# main.net
KiCad netlist of a schematic drawn in Altium Designer
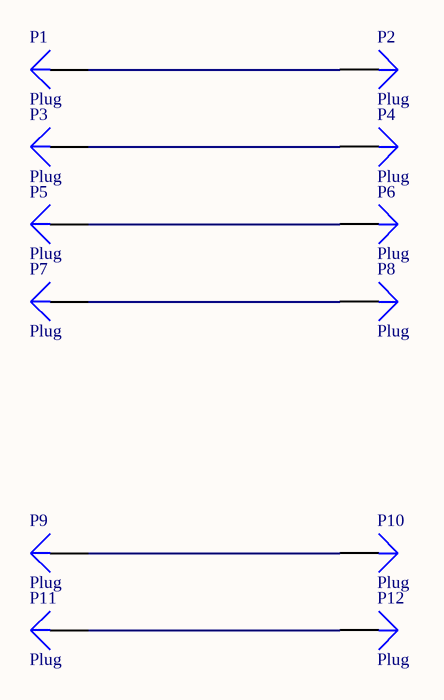
[diagram p0: main.SchDoc]

(export (version "E")
  (design (tool "Eeschema 10.0.6"))
  (components
    (comp (ref "P1")
      (value "Plug")
      (footprint "PIN_CONN")
      (fields (field (name "PUBLISHER") "Altium Limited"))
      (libsource (lib "Miscellaneous Connectors") (part "Plug"))
    )
    (comp (ref "P2")
      (value "Plug")
      (footprint "PIN_CONN")
      (fields (field (name "PUBLISHER") "Altium Limited"))
      (libsource (lib "Miscellaneous Connectors") (part "Plug"))
    )
    (comp (ref "P3")
      (value "Plug")
      (footprint "PIN_CONN")
      (fields (field (name "PUBLISHER") "Altium Limited"))
      (libsource (lib "Miscellaneous Connectors") (part "Plug"))
    )
    (comp (ref "P4")
      (value "Plug")
      (footprint "PIN_CONN")
      (fields (field (name "PUBLISHER") "Altium Limited"))
      (libsource (lib "Miscellaneous Connectors") (part "Plug"))
    )
    (comp (ref "P5")
      (value "Plug")
      (footprint "PIN_CONN")
      (fields (field (name "PUBLISHER") "Altium Limited"))
      (libsource (lib "Miscellaneous Connectors") (part "Plug"))
    )
    (comp (ref "P6")
      (value "Plug")
      (footprint "PIN_CONN")
      (fields (field (name "PUBLISHER") "Altium Limited"))
      (libsource (lib "Miscellaneous Connectors") (part "Plug"))
    )
    (comp (ref "P7")
      (value "Plug")
      (footprint "PIN_CONN")
      (fields (field (name "PUBLISHER") "Altium Limited"))
      (libsource (lib "Miscellaneous Connectors") (part "Plug"))
    )
    (comp (ref "P8")
      (value "Plug")
      (footprint "PIN_CONN")
      (fields (field (name "PUBLISHER") "Altium Limited"))
      (libsource (lib "Miscellaneous Connectors") (part "Plug"))
    )
    (comp (ref "P9")
      (value "Plug")
      (footprint "PIN_CONN")
      (fields (field (name "PUBLISHER") "Altium Limited"))
      (libsource (lib "Miscellaneous Connectors") (part "Plug"))
    )
    (comp (ref "P10")
      (value "Plug")
      (footprint "PIN_CONN")
      (fields (field (name "PUBLISHER") "Altium Limited"))
      (libsource (lib "Miscellaneous Connectors") (part "Plug"))
    )
    (comp (ref "P11")
      (value "Plug")
      (footprint "PIN_CONN")
      (fields (field (name "PUBLISHER") "Altium Limited"))
      (libsource (lib "Miscellaneous Connectors") (part "Plug"))
    )
    (comp (ref "P12")
      (value "Plug")
      (footprint "PIN_CONN")
      (fields (field (name "PUBLISHER") "Altium Limited"))
      (libsource (lib "Miscellaneous Connectors") (part "Plug"))
    )
  )
  (nets
    (net (code "1") (name "Net-(P1-Pad1)") (class "Default")
      (node (ref "P1") (pin "1") (pinfunction "1_1") (pintype "passive"))
      (node (ref "P2") (pin "1") (pinfunction "1_1") (pintype "passive"))
    )
    (net (code "2") (name "Net-(P3-Pad1)") (class "Default")
      (node (ref "P3") (pin "1") (pinfunction "1_1") (pintype "passive"))
      (node (ref "P4") (pin "1") (pinfunction "1_1") (pintype "passive"))
    )
    (net (code "3") (name "Net-(P5-Pad1)") (class "Default")
      (node (ref "P5") (pin "1") (pinfunction "1_1") (pintype "passive"))
      (node (ref "P6") (pin "1") (pinfunction "1_1") (pintype "passive"))
    )
    (net (code "4") (name "Net-(P7-Pad1)") (class "Default")
      (node (ref "P7") (pin "1") (pinfunction "1_1") (pintype "passive"))
      (node (ref "P8") (pin "1") (pinfunction "1_1") (pintype "passive"))
    )
    (net (code "5") (name "Net-(P10-Pad1)") (class "Default")
      (node (ref "P10") (pin "1") (pinfunction "1_1") (pintype "passive"))
      (node (ref "P9") (pin "1") (pinfunction "1_1") (pintype "passive"))
    )
    (net (code "6") (name "Net-(P11-Pad1)") (class "Default")
      (node (ref "P11") (pin "1") (pinfunction "1_1") (pintype "passive"))
      (node (ref "P12") (pin "1") (pinfunction "1_1") (pintype "passive"))
    )
  )
)
